# Sensor.net
KiCad netlist of a schematic drawn in Altium Designer
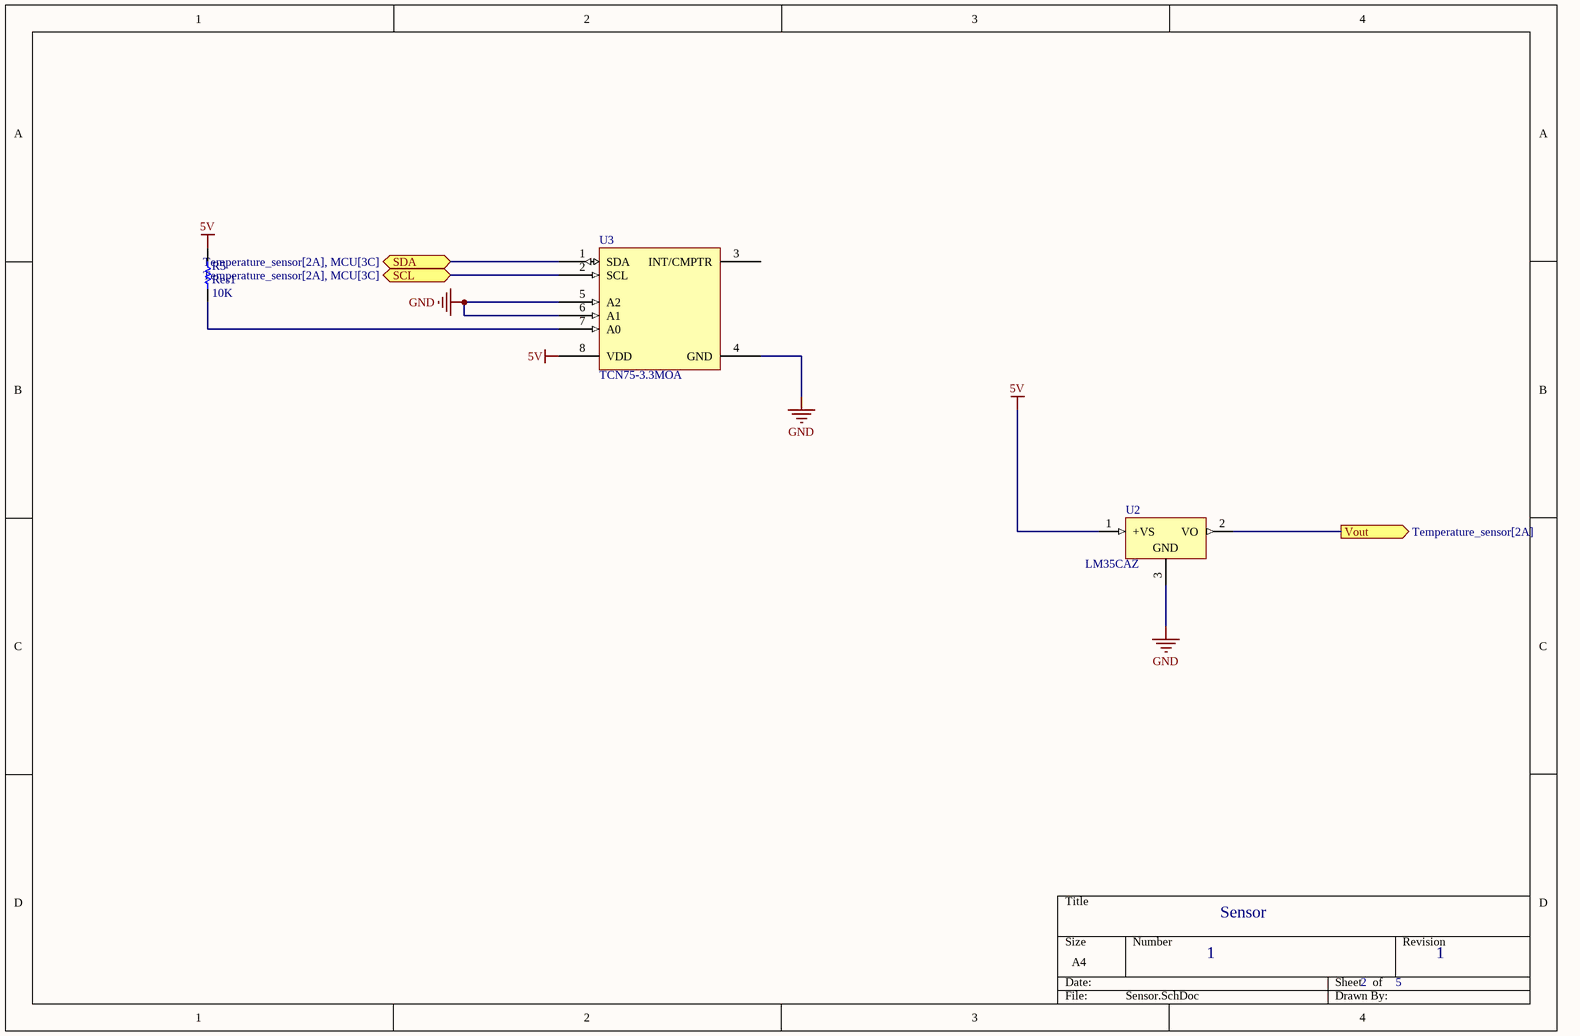
[diagram p0: Sensor.SchDoc]

(export (version "E")
  (design (tool "Eeschema 10.0.6"))
  (components
    (comp (ref "R5")
      (value "Res1")
      (footprint "0805")
      (description "Resistor")
      (fields (field (name "ALTIUM_VALUE") "10K") (field (name "PUBLISHER") "Altium Limited"))
      (libsource (lib "Miscellaneous Devices") (part "Res1"))
    )
    (comp (ref "U2")
      (value "LM35CAZ")
      (footprint "Z03A")
      (description "Precision Centigrade Temperature Sensor, 3-pin TO-92")
      (fields
        (field (name "MANUFACTURER") "National Semiconductor")
        (field (name "PUBLISHER") "Altium Limited")
      )
      (libsource (lib "NSC Temperature Sensor") (part "LM35CAZ"))
    )
    (comp (ref "U3")
      (value "TCN75-3.3MOA")
      (footprint "SOIC127P600X175-8N")
      (libsource (lib "TCN75") (part "TCN75"))
    )
  )
  (nets
    (net (code "1") (name "/SCL") (class "Default")
      (node (ref "U3") (pin "2") (pinfunction "SCL_2") (pintype "input"))
    )
    (net (code "2") (name "/SDA") (class "Default")
      (node (ref "U3") (pin "1") (pinfunction "SDA_1") (pintype "bidirectional"))
    )
    (net (code "3") (name "/Vout") (class "Default")
      (node (ref "U2") (pin "2") (pinfunction "VO_2") (pintype "output"))
    )
    (net (code "4") (name "5V") (class "Default")
      (node (ref "R5") (pin "2") (pinfunction "2_2") (pintype "passive"))
      (node (ref "U2") (pin "1") (pinfunction "+VS_1") (pintype "input"))
      (node (ref "U3") (pin "8") (pinfunction "VDD_8") (pintype "passive"))
    )
    (net (code "5") (name "GND") (class "Default")
      (node (ref "U2") (pin "3") (pinfunction "GND_3") (pintype "power_in"))
      (node (ref "U3") (pin "4") (pinfunction "GND_4") (pintype "passive"))
      (node (ref "U3") (pin "5") (pinfunction "A2_5") (pintype "input"))
      (node (ref "U3") (pin "6") (pinfunction "A1_6") (pintype "input"))
    )
    (net (code "6") (name "Net-(U3-A0)") (class "Default")
      (node (ref "R5") (pin "1") (pinfunction "1_1") (pintype "passive"))
      (node (ref "U3") (pin "7") (pinfunction "A0_7") (pintype "input"))
    )
    (net (code "7") (name "unconnected-(U3-INT{slash}CMPTR-Pad3)") (class "Default")
      (node (ref "U3") (pin "3") (pinfunction "INT/CMPTR_3") (pintype "passive"))
    )
  )
)
